# SIM_NB_IoT.net
KiCad netlist of a schematic drawn in Altium Designer
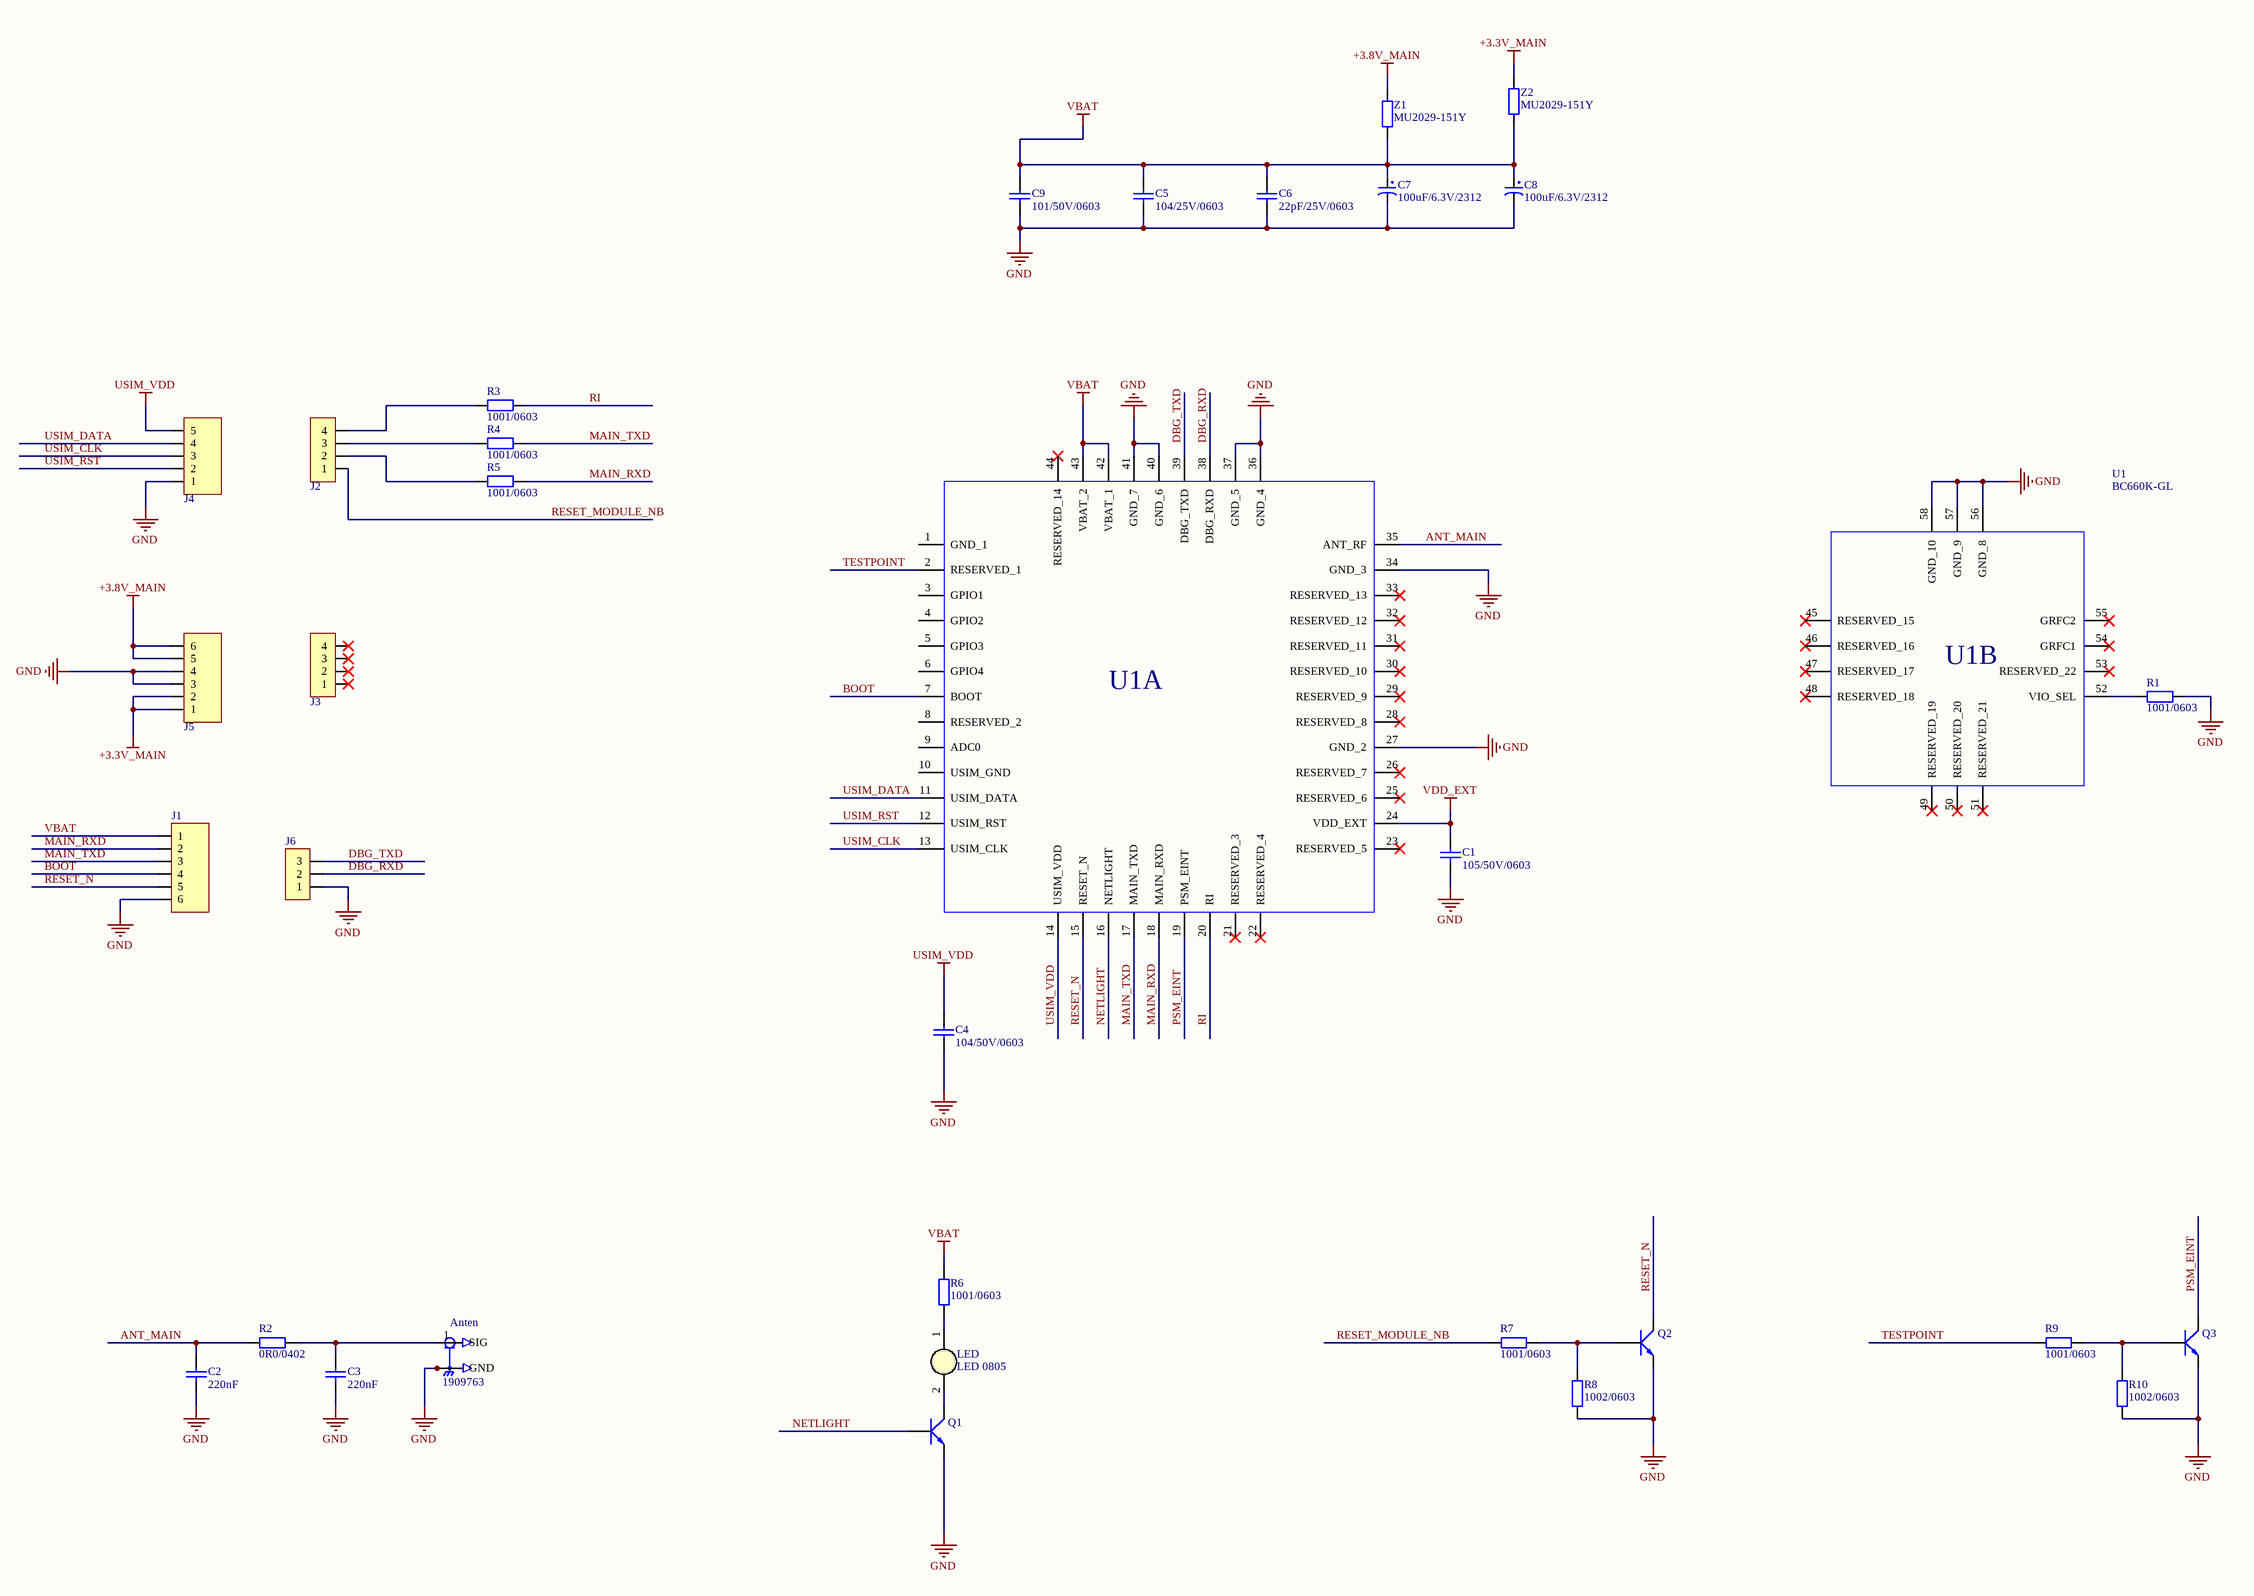
[diagram p0: SIM_NB_IoT.SchDoc]

(export (version "E")
  (design (tool "Eeschema 10.0.6"))
  (components
    (comp (ref "Anten")
      (value "1909763")
      (footprint "TE_1909763-1")
      (description "VAO ITEM, MINI RF HEADER")
      (fields (field (name "MP") "1909763-1"))
      (libsource (lib "Labrary_Tu_Nguon_Version2") (part "Antenna"))
    )
    (comp (ref "C1")
      (value "105/50V/0603")
      (footprint "tu 0603")
      (description "Dán")
      (libsource (lib "Altium_Lib_by_KhueNguyenCreator") (part "Tu 0603 563 16V 10%"))
    )
    (comp (ref "C2")
      (value "220nF")
      (footprint "tu 0402")
      (description "Dán")
      (libsource (lib "Altium_Lib_by_KhueNguyenCreator") (part "Tu 0402 220nF 6.3V 20%"))
    )
    (comp (ref "C3")
      (value "220nF")
      (footprint "tu 0402")
      (description "Dán")
      (libsource (lib "Altium_Lib_by_KhueNguyenCreator") (part "Tu 0402 220nF 6.3V 20%"))
    )
    (comp (ref "C4")
      (value "104/50V/0603")
      (footprint "tu 0603")
      (description "Dán")
      (libsource (lib "Altium_Lib_by_KhueNguyenCreator") (part "Tu 0603 563 16V 10%"))
    )
    (comp (ref "C5")
      (value "104/25V/0603")
      (footprint "tu 0603")
      (description "Dán")
      (libsource (lib "Altium_Lib_by_KhueNguyenCreator") (part "Tu 0603 563 16V 10%"))
    )
    (comp (ref "C6")
      (value "22pF/25V/0603")
      (footprint "tu 0603")
      (description "Dán")
      (libsource (lib "Altium_Lib_by_KhueNguyenCreator") (part "Tu 0603 563 16V 10%"))
    )
    (comp (ref "C7")
      (value "100uF/6.3V/2312")
      (footprint "tu tantalum smd3216")
      (description "Dán")
      (libsource (lib "Altium_Lib_by_KhueNguyenCreator") (part "Tu tantalum 10uF 16V SMD3216"))
    )
    (comp (ref "C8")
      (value "100uF/6.3V/2312")
      (footprint "tu tantalum smd3216")
      (description "Dán")
      (libsource (lib "Altium_Lib_by_KhueNguyenCreator") (part "Tu tantalum 10uF 16V SMD3216"))
    )
    (comp (ref "C9")
      (value "101/50V/0603")
      (footprint "tu 0603")
      (description "Dán")
      (libsource (lib "Altium_Lib_by_KhueNguyenCreator") (part "Tu 0603 563 16V 10%"))
    )
    (comp (ref "J1")
      (value "JP 1x6 2.54")
      (footprint "JP 1x6 DT")
      (description "Cắm")
      (libsource (lib "Altium_Lib_by_KhueNguyenCreator") (part "JP 1x6 2.54 Duc Thang"))
    )
    (comp (ref "J2")
      (value "JP 1x4 2.54")
      (footprint "JP 1x4 DT")
      (description "Cắm")
      (libsource (lib "Altium_Lib_by_KhueNguyenCreator") (part "JP 1x4 2.54 Duc Thang"))
    )
    (comp (ref "J3")
      (value "JP 1x4 2.54")
      (footprint "JP 1x4 DT")
      (description "Cắm")
      (libsource (lib "Altium_Lib_by_KhueNguyenCreator") (part "JP 1x4 2.54 Duc Thang"))
    )
    (comp (ref "J4")
      (value "JP 1x5 2.54")
      (footprint "JP 1x5 DT")
      (description "Cắm")
      (libsource (lib "Altium_Lib_by_KhueNguyenCreator") (part "JP 1x5 2.54 Duc Thang"))
    )
    (comp (ref "J5")
      (value "JP 1x6 2.54")
      (footprint "JP 1x6 DT")
      (description "Cắm")
      (libsource (lib "") (part "JP 1x6 2.54 Duc Thang_1"))
    )
    (comp (ref "J6")
      (value "JP 1x3 2.54")
      (footprint "JP 1x3 DT")
      (description "Cắm")
      (libsource (lib "Altium_Lib_by_KhueNguyenCreator") (part "JP 1x3 2.54 Duc Thang"))
    )
    (comp (ref "LED")
      (value "LED 0805")
      (footprint "LED-0805-Yellow")
      (description "Dán")
      (libsource (lib "Altium_Lib_by_KhueNguyenCreator") (part "LED 0805 Trang"))
    )
    (comp (ref "Q1")
      (value "HF")
      (footprint "SOT23")
      (description "NPN transistor")
      (libsource (lib "Altium_Lib_by_KhueNguyenCreator") (part "C1815 HF SMD"))
    )
    (comp (ref "Q2")
      (value "HF")
      (footprint "SOT23")
      (description "NPN transistor")
      (libsource (lib "Altium_Lib_by_KhueNguyenCreator") (part "C1815 HF SMD"))
    )
    (comp (ref "Q3")
      (value "HF")
      (footprint "SOT23")
      (description "NPN transistor")
      (libsource (lib "Altium_Lib_by_KhueNguyenCreator") (part "C1815 HF SMD"))
    )
    (comp (ref "R1")
      (value "1001/0603")
      (footprint "tro smd 0603")
      (description "Dán")
      (libsource (lib "Altium_Lib_by_KhueNguyenCreator") (part "Tro 0603 5% 510R"))
    )
    (comp (ref "R2")
      (value "0R0/0402")
      (footprint "tro smd 0603")
      (description "Dán")
      (libsource (lib "Altium_Lib_by_KhueNguyenCreator") (part "Tro 0603 5% 510R"))
    )
    (comp (ref "R3")
      (value "1001/0603")
      (footprint "tro smd 0603")
      (description "Dán")
      (libsource (lib "Altium_Lib_by_KhueNguyenCreator") (part "Tro 0603 5% 510R"))
    )
    (comp (ref "R4")
      (value "1001/0603")
      (footprint "tro smd 0603")
      (description "Dán")
      (libsource (lib "Altium_Lib_by_KhueNguyenCreator") (part "Tro 0603 5% 510R"))
    )
    (comp (ref "R5")
      (value "1001/0603")
      (footprint "tro smd 0603")
      (description "Dán")
      (libsource (lib "Altium_Lib_by_KhueNguyenCreator") (part "Tro 0603 5% 510R"))
    )
    (comp (ref "R6")
      (value "1001/0603")
      (footprint "tro smd 0603")
      (description "Dán")
      (libsource (lib "Altium_Lib_by_KhueNguyenCreator") (part "Tro 0603 5% 510R"))
    )
    (comp (ref "R7")
      (value "1001/0603")
      (footprint "tro smd 0603")
      (description "Dán")
      (libsource (lib "Altium_Lib_by_KhueNguyenCreator") (part "Tro 0603 5% 510R"))
    )
    (comp (ref "R8")
      (value "1002/0603")
      (footprint "tro smd 0603")
      (description "Dán")
      (libsource (lib "Altium_Lib_by_KhueNguyenCreator") (part "Tro 0603 5% 510R"))
    )
    (comp (ref "R9")
      (value "1001/0603")
      (footprint "tro smd 0603")
      (description "Dán")
      (libsource (lib "Altium_Lib_by_KhueNguyenCreator") (part "Tro 0603 5% 510R"))
    )
    (comp (ref "R10")
      (value "1002/0603")
      (footprint "tro smd 0603")
      (description "Dán")
      (libsource (lib "Altium_Lib_by_KhueNguyenCreator") (part "Tro 0603 5% 510R"))
    )
    (comp (ref "U1")
      (value "BC660K-GL")
      (footprint "BC660KGL")
      (libsource (lib "Labrary_Tu_Nguon_Version2") (part "BC660K-GL"))
    )
    (comp (ref "Z1")
      (value "MU2029-151Y")
      (footprint "MU2029151Y")
      (description "150 Ohms @ 100 MHz 1 Power, Signal Line Ferrite Bead 0805 (2012 Metric) 800mA 200mOhm")
      (fields (field (name "MOUSER PART NUMBER") "652-MU2029-151Y"))
      (libsource (lib "Labrary_Tu_Nguon_Version2") (part "MU2029-151Y"))
    )
    (comp (ref "Z2")
      (value "MU2029-151Y")
      (footprint "MU2029151Y")
      (description "150 Ohms @ 100 MHz 1 Power, Signal Line Ferrite Bead 0805 (2012 Metric) 800mA 200mOhm")
      (fields (field (name "MOUSER PART NUMBER") "652-MU2029-151Y"))
      (libsource (lib "Labrary_Tu_Nguon_Version2") (part "MU2029-151Y"))
    )
  )
  (nets
    (net (code "1") (name "+3.3V_MAIN") (class "Default")
      (node (ref "J5") (pin "1") (pinfunction "1_1") (pintype "passive"))
      (node (ref "J5") (pin "2") (pinfunction "2_2") (pintype "passive"))
      (node (ref "Z2") (pin "2") (pinfunction "2_2") (pintype "passive"))
    )
    (net (code "2") (name "+3.8V_MAIN") (class "Default")
      (node (ref "J5") (pin "5") (pinfunction "5_5") (pintype "passive"))
      (node (ref "J5") (pin "6") (pinfunction "6_6") (pintype "passive"))
      (node (ref "Z1") (pin "2") (pinfunction "2_2") (pintype "passive"))
    )
    (net (code "3") (name "/ANT_MAIN") (class "Default")
      (node (ref "C2") (pin "2") (pinfunction "2_2") (pintype "passive"))
      (node (ref "R2") (pin "1") (pinfunction "1_1") (pintype "passive"))
      (node (ref "U1") (pin "35") (pinfunction "ANT_RF_35") (pintype "passive"))
    )
    (net (code "4") (name "/BOOT") (class "Default")
      (node (ref "J1") (pin "4") (pinfunction "4_4") (pintype "passive"))
      (node (ref "U1") (pin "7") (pinfunction "BOOT_7") (pintype "passive"))
    )
    (net (code "5") (name "/DBG_RXD") (class "Default")
      (node (ref "J6") (pin "2") (pinfunction "2_2") (pintype "passive"))
      (node (ref "U1") (pin "38") (pinfunction "DBG_RXD_38") (pintype "passive"))
    )
    (net (code "6") (name "/DBG_TXD") (class "Default")
      (node (ref "J6") (pin "3") (pinfunction "3_3") (pintype "passive"))
      (node (ref "U1") (pin "39") (pinfunction "DBG_TXD_39") (pintype "passive"))
    )
    (net (code "7") (name "/MAIN_RXD") (class "Default")
      (node (ref "J1") (pin "2") (pinfunction "2_2") (pintype "passive"))
      (node (ref "R5") (pin "1") (pinfunction "1_1") (pintype "passive"))
      (node (ref "U1") (pin "18") (pinfunction "MAIN_RXD_18") (pintype "passive"))
    )
    (net (code "8") (name "/MAIN_TXD") (class "Default")
      (node (ref "J1") (pin "3") (pinfunction "3_3") (pintype "passive"))
      (node (ref "R4") (pin "1") (pinfunction "1_1") (pintype "passive"))
      (node (ref "U1") (pin "17") (pinfunction "MAIN_TXD_17") (pintype "passive"))
    )
    (net (code "9") (name "/NETLIGHT") (class "Default")
      (node (ref "Q1") (pin "1") (pinfunction "B_1") (pintype "passive"))
      (node (ref "U1") (pin "16") (pinfunction "NETLIGHT_16") (pintype "passive"))
    )
    (net (code "10") (name "/PSM_EINT") (class "Default")
      (node (ref "Q3") (pin "3") (pinfunction "C_3") (pintype "passive"))
      (node (ref "U1") (pin "19") (pinfunction "PSM_EINT_19") (pintype "passive"))
    )
    (net (code "11") (name "/RESET_MODULE_NB") (class "Default")
      (node (ref "J2") (pin "1") (pinfunction "1_1") (pintype "passive"))
      (node (ref "R7") (pin "2") (pinfunction "2_2") (pintype "passive"))
    )
    (net (code "12") (name "/RESET_N") (class "Default")
      (node (ref "J1") (pin "5") (pinfunction "5_5") (pintype "passive"))
      (node (ref "Q2") (pin "3") (pinfunction "C_3") (pintype "passive"))
      (node (ref "U1") (pin "15") (pinfunction "RESET_N_15") (pintype "passive"))
    )
    (net (code "13") (name "/RI") (class "Default")
      (node (ref "R3") (pin "1") (pinfunction "1_1") (pintype "passive"))
      (node (ref "U1") (pin "20") (pinfunction "RI_20") (pintype "passive"))
    )
    (net (code "14") (name "/TESTPOINT") (class "Default")
      (node (ref "R9") (pin "2") (pinfunction "2_2") (pintype "passive"))
      (node (ref "U1") (pin "2") (pinfunction "RESERVED_1_2") (pintype "passive"))
    )
    (net (code "15") (name "/USIM_CLK") (class "Default")
      (node (ref "J4") (pin "3") (pinfunction "3_3") (pintype "passive"))
      (node (ref "U1") (pin "13") (pinfunction "USIM_CLK_13") (pintype "passive"))
    )
    (net (code "16") (name "/USIM_DATA") (class "Default")
      (node (ref "J4") (pin "4") (pinfunction "4_4") (pintype "passive"))
      (node (ref "U1") (pin "11") (pinfunction "USIM_DATA_11") (pintype "passive"))
    )
    (net (code "17") (name "/USIM_RST") (class "Default")
      (node (ref "J4") (pin "2") (pinfunction "2_2") (pintype "passive"))
      (node (ref "U1") (pin "12") (pinfunction "USIM_RST_12") (pintype "passive"))
    )
    (net (code "18") (name "GND") (class "Default")
      (node (ref "Anten") (pin "2") (pinfunction "GND_2") (pintype "passive"))
      (node (ref "Anten") (pin "3") (pinfunction "GND_3") (pintype "passive"))
      (node (ref "C1") (pin "2") (pinfunction "2_2") (pintype "passive"))
      (node (ref "C2") (pin "1") (pinfunction "1_1") (pintype "passive"))
      (node (ref "C3") (pin "1") (pinfunction "1_1") (pintype "passive"))
      (node (ref "C4") (pin "2") (pinfunction "2_2") (pintype "passive"))
      (node (ref "C5") (pin "2") (pinfunction "2_2") (pintype "passive"))
      (node (ref "C6") (pin "2") (pinfunction "2_2") (pintype "passive"))
      (node (ref "C7") (pin "2") (pinfunction "2_2") (pintype "passive"))
      (node (ref "C8") (pin "2") (pinfunction "2_2") (pintype "passive"))
      (node (ref "C9") (pin "2") (pinfunction "2_2") (pintype "passive"))
      (node (ref "J1") (pin "6") (pinfunction "6_6") (pintype "passive"))
      (node (ref "J4") (pin "1") (pinfunction "1_1") (pintype "passive"))
      (node (ref "J5") (pin "3") (pinfunction "3_3") (pintype "passive"))
      (node (ref "J5") (pin "4") (pinfunction "4_4") (pintype "passive"))
      (node (ref "J6") (pin "1") (pinfunction "1_1") (pintype "passive"))
      (node (ref "Q1") (pin "2") (pinfunction "E_2") (pintype "passive"))
      (node (ref "Q2") (pin "2") (pinfunction "E_2") (pintype "passive"))
      (node (ref "Q3") (pin "2") (pinfunction "E_2") (pintype "passive"))
      (node (ref "R1") (pin "2") (pinfunction "2_2") (pintype "passive"))
      (node (ref "R10") (pin "2") (pinfunction "2_2") (pintype "passive"))
      (node (ref "R8") (pin "2") (pinfunction "2_2") (pintype "passive"))
      (node (ref "U1") (pin "27") (pinfunction "GND_2_27") (pintype "passive"))
      (node (ref "U1") (pin "34") (pinfunction "GND_3_34") (pintype "passive"))
      (node (ref "U1") (pin "36") (pinfunction "GND_4_36") (pintype "passive"))
      (node (ref "U1") (pin "37") (pinfunction "GND_5_37") (pintype "passive"))
      (node (ref "U1") (pin "40") (pinfunction "GND_6_40") (pintype "passive"))
      (node (ref "U1") (pin "41") (pinfunction "GND_7_41") (pintype "passive"))
      (node (ref "U1") (pin "56") (pinfunction "GND_8_56") (pintype "passive"))
      (node (ref "U1") (pin "57") (pinfunction "GND_9_57") (pintype "passive"))
      (node (ref "U1") (pin "58") (pinfunction "GND_10_58") (pintype "passive"))
    )
    (net (code "19") (name "Net-(Anten-SIG)") (class "Default")
      (node (ref "Anten") (pin "1") (pinfunction "SIG_1") (pintype "passive"))
      (node (ref "C3") (pin "2") (pinfunction "2_2") (pintype "passive"))
      (node (ref "R2") (pin "2") (pinfunction "2_2") (pintype "passive"))
    )
    (net (code "20") (name "Net-(J2-Pad2)") (class "Default")
      (node (ref "J2") (pin "2") (pinfunction "2_2") (pintype "passive"))
      (node (ref "R5") (pin "2") (pinfunction "2_2") (pintype "passive"))
    )
    (net (code "21") (name "Net-(J2-Pad3)") (class "Default")
      (node (ref "J2") (pin "3") (pinfunction "3_3") (pintype "passive"))
      (node (ref "R4") (pin "2") (pinfunction "2_2") (pintype "passive"))
    )
    (net (code "22") (name "Net-(J2-Pad4)") (class "Default")
      (node (ref "J2") (pin "4") (pinfunction "4_4") (pintype "passive"))
      (node (ref "R3") (pin "2") (pinfunction "2_2") (pintype "passive"))
    )
    (net (code "23") (name "Net-(LED-A)") (class "Default")
      (node (ref "LED") (pin "1") (pinfunction "A_1") (pintype "passive"))
      (node (ref "R6") (pin "2") (pinfunction "2_2") (pintype "passive"))
    )
    (net (code "24") (name "Net-(LED-K)") (class "Default")
      (node (ref "LED") (pin "2") (pinfunction "K_2") (pintype "passive"))
      (node (ref "Q1") (pin "3") (pinfunction "C_3") (pintype "passive"))
    )
    (net (code "25") (name "Net-(Q2-B)") (class "Default")
      (node (ref "Q2") (pin "1") (pinfunction "B_1") (pintype "passive"))
      (node (ref "R7") (pin "1") (pinfunction "1_1") (pintype "passive"))
      (node (ref "R8") (pin "1") (pinfunction "1_1") (pintype "passive"))
    )
    (net (code "26") (name "Net-(Q3-B)") (class "Default")
      (node (ref "Q3") (pin "1") (pinfunction "B_1") (pintype "passive"))
      (node (ref "R10") (pin "1") (pinfunction "1_1") (pintype "passive"))
      (node (ref "R9") (pin "1") (pinfunction "1_1") (pintype "passive"))
    )
    (net (code "27") (name "Net-(U1-VIO_SEL)") (class "Default")
      (node (ref "R1") (pin "1") (pinfunction "1_1") (pintype "passive"))
      (node (ref "U1") (pin "52") (pinfunction "VIO_SEL_52") (pintype "passive"))
    )
    (net (code "28") (name "USIM_VDD") (class "Default")
      (node (ref "C4") (pin "1") (pinfunction "1_1") (pintype "passive"))
      (node (ref "J4") (pin "5") (pinfunction "5_5") (pintype "passive"))
      (node (ref "U1") (pin "14") (pinfunction "USIM_VDD_14") (pintype "passive"))
    )
    (net (code "29") (name "VBAT") (class "Default")
      (node (ref "C5") (pin "1") (pinfunction "1_1") (pintype "passive"))
      (node (ref "C6") (pin "1") (pinfunction "1_1") (pintype "passive"))
      (node (ref "C7") (pin "1") (pinfunction "1_1") (pintype "passive"))
      (node (ref "C8") (pin "1") (pinfunction "1_1") (pintype "passive"))
      (node (ref "C9") (pin "1") (pinfunction "1_1") (pintype "passive"))
      (node (ref "J1") (pin "1") (pinfunction "1_1") (pintype "passive"))
      (node (ref "R6") (pin "1") (pinfunction "1_1") (pintype "passive"))
      (node (ref "U1") (pin "42") (pinfunction "VBAT_1_42") (pintype "passive"))
      (node (ref "U1") (pin "43") (pinfunction "VBAT_2_43") (pintype "passive"))
      (node (ref "Z1") (pin "1") (pinfunction "1_1") (pintype "passive"))
      (node (ref "Z2") (pin "1") (pinfunction "1_1") (pintype "passive"))
    )
    (net (code "30") (name "VDD_EXT") (class "Default")
      (node (ref "C1") (pin "1") (pinfunction "1_1") (pintype "passive"))
      (node (ref "U1") (pin "24") (pinfunction "VDD_EXT_24") (pintype "passive"))
    )
    (net (code "31") (name "unconnected-(J3-Pad1)") (class "Default")
      (node (ref "J3") (pin "1") (pinfunction "1_1") (pintype "passive+no_connect"))
    )
    (net (code "32") (name "unconnected-(J3-Pad2)") (class "Default")
      (node (ref "J3") (pin "2") (pinfunction "2_2") (pintype "passive+no_connect"))
    )
    (net (code "33") (name "unconnected-(J3-Pad3)") (class "Default")
      (node (ref "J3") (pin "3") (pinfunction "3_3") (pintype "passive+no_connect"))
    )
    (net (code "34") (name "unconnected-(J3-Pad4)") (class "Default")
      (node (ref "J3") (pin "4") (pinfunction "4_4") (pintype "passive+no_connect"))
    )
    (net (code "35") (name "unconnected-(U1-ADC0-Pad9)") (class "Default")
      (node (ref "U1") (pin "9") (pinfunction "ADC0_9") (pintype "passive"))
    )
    (net (code "36") (name "unconnected-(U1-GND_1-Pad1)") (class "Default")
      (node (ref "U1") (pin "1") (pinfunction "GND_1_1") (pintype "passive"))
    )
    (net (code "37") (name "unconnected-(U1-GPIO1-Pad3)") (class "Default")
      (node (ref "U1") (pin "3") (pinfunction "GPIO1_3") (pintype "passive"))
    )
    (net (code "38") (name "unconnected-(U1-GPIO2-Pad4)") (class "Default")
      (node (ref "U1") (pin "4") (pinfunction "GPIO2_4") (pintype "passive"))
    )
    (net (code "39") (name "unconnected-(U1-GPIO3-Pad5)") (class "Default")
      (node (ref "U1") (pin "5") (pinfunction "GPIO3_5") (pintype "passive"))
    )
    (net (code "40") (name "unconnected-(U1-GPIO4-Pad6)") (class "Default")
      (node (ref "U1") (pin "6") (pinfunction "GPIO4_6") (pintype "passive"))
    )
    (net (code "41") (name "unconnected-(U1-GRFC1-Pad54)") (class "Default")
      (node (ref "U1") (pin "54") (pinfunction "GRFC1_54") (pintype "passive+no_connect"))
    )
    (net (code "42") (name "unconnected-(U1-GRFC2-Pad55)") (class "Default")
      (node (ref "U1") (pin "55") (pinfunction "GRFC2_55") (pintype "passive+no_connect"))
    )
    (net (code "43") (name "unconnected-(U1-RESERVED_2-Pad8)") (class "Default")
      (node (ref "U1") (pin "8") (pinfunction "RESERVED_2_8") (pintype "passive"))
    )
    (net (code "44") (name "unconnected-(U1-RESERVED_3-Pad21)") (class "Default")
      (node (ref "U1") (pin "21") (pinfunction "RESERVED_3_21") (pintype "passive+no_connect"))
    )
    (net (code "45") (name "unconnected-(U1-RESERVED_4-Pad22)") (class "Default")
      (node (ref "U1") (pin "22") (pinfunction "RESERVED_4_22") (pintype "passive+no_connect"))
    )
    (net (code "46") (name "unconnected-(U1-RESERVED_5-Pad23)") (class "Default")
      (node (ref "U1") (pin "23") (pinfunction "RESERVED_5_23") (pintype "passive+no_connect"))
    )
    (net (code "47") (name "unconnected-(U1-RESERVED_6-Pad25)") (class "Default")
      (node (ref "U1") (pin "25") (pinfunction "RESERVED_6_25") (pintype "passive+no_connect"))
    )
    (net (code "48") (name "unconnected-(U1-RESERVED_7-Pad26)") (class "Default")
      (node (ref "U1") (pin "26") (pinfunction "RESERVED_7_26") (pintype "passive+no_connect"))
    )
    (net (code "49") (name "unconnected-(U1-RESERVED_8-Pad28)") (class "Default")
      (node (ref "U1") (pin "28") (pinfunction "RESERVED_8_28") (pintype "passive+no_connect"))
    )
    (net (code "50") (name "unconnected-(U1-RESERVED_9-Pad29)") (class "Default")
      (node (ref "U1") (pin "29") (pinfunction "RESERVED_9_29") (pintype "passive+no_connect"))
    )
    (net (code "51") (name "unconnected-(U1-RESERVED_10-Pad30)") (class "Default")
      (node (ref "U1") (pin "30") (pinfunction "RESERVED_10_30") (pintype "passive+no_connect"))
    )
    (net (code "52") (name "unconnected-(U1-RESERVED_11-Pad31)") (class "Default")
      (node (ref "U1") (pin "31") (pinfunction "RESERVED_11_31") (pintype "passive+no_connect"))
    )
    (net (code "53") (name "unconnected-(U1-RESERVED_12-Pad32)") (class "Default")
      (node (ref "U1") (pin "32") (pinfunction "RESERVED_12_32") (pintype "passive+no_connect"))
    )
    (net (code "54") (name "unconnected-(U1-RESERVED_13-Pad33)") (class "Default")
      (node (ref "U1") (pin "33") (pinfunction "RESERVED_13_33") (pintype "passive+no_connect"))
    )
    (net (code "55") (name "unconnected-(U1-RESERVED_14-Pad44)") (class "Default")
      (node (ref "U1") (pin "44") (pinfunction "RESERVED_14_44") (pintype "passive+no_connect"))
    )
    (net (code "56") (name "unconnected-(U1-RESERVED_15-Pad45)") (class "Default")
      (node (ref "U1") (pin "45") (pinfunction "RESERVED_15_45") (pintype "passive+no_connect"))
    )
    (net (code "57") (name "unconnected-(U1-RESERVED_16-Pad46)") (class "Default")
      (node (ref "U1") (pin "46") (pinfunction "RESERVED_16_46") (pintype "passive+no_connect"))
    )
    (net (code "58") (name "unconnected-(U1-RESERVED_17-Pad47)") (class "Default")
      (node (ref "U1") (pin "47") (pinfunction "RESERVED_17_47") (pintype "passive+no_connect"))
    )
    (net (code "59") (name "unconnected-(U1-RESERVED_18-Pad48)") (class "Default")
      (node (ref "U1") (pin "48") (pinfunction "RESERVED_18_48") (pintype "passive+no_connect"))
    )
    (net (code "60") (name "unconnected-(U1-RESERVED_19-Pad49)") (class "Default")
      (node (ref "U1") (pin "49") (pinfunction "RESERVED_19_49") (pintype "passive+no_connect"))
    )
    (net (code "61") (name "unconnected-(U1-RESERVED_20-Pad50)") (class "Default")
      (node (ref "U1") (pin "50") (pinfunction "RESERVED_20_50") (pintype "passive+no_connect"))
    )
    (net (code "62") (name "unconnected-(U1-RESERVED_21-Pad51)") (class "Default")
      (node (ref "U1") (pin "51") (pinfunction "RESERVED_21_51") (pintype "passive+no_connect"))
    )
    (net (code "63") (name "unconnected-(U1-RESERVED_22-Pad53)") (class "Default")
      (node (ref "U1") (pin "53") (pinfunction "RESERVED_22_53") (pintype "passive+no_connect"))
    )
    (net (code "64") (name "unconnected-(U1-USIM_GND-Pad10)") (class "Default")
      (node (ref "U1") (pin "10") (pinfunction "USIM_GND_10") (pintype "passive"))
    )
  )
)
